# MXR_Microamp.net
KiCad netlist of a schematic drawn in EAGLE
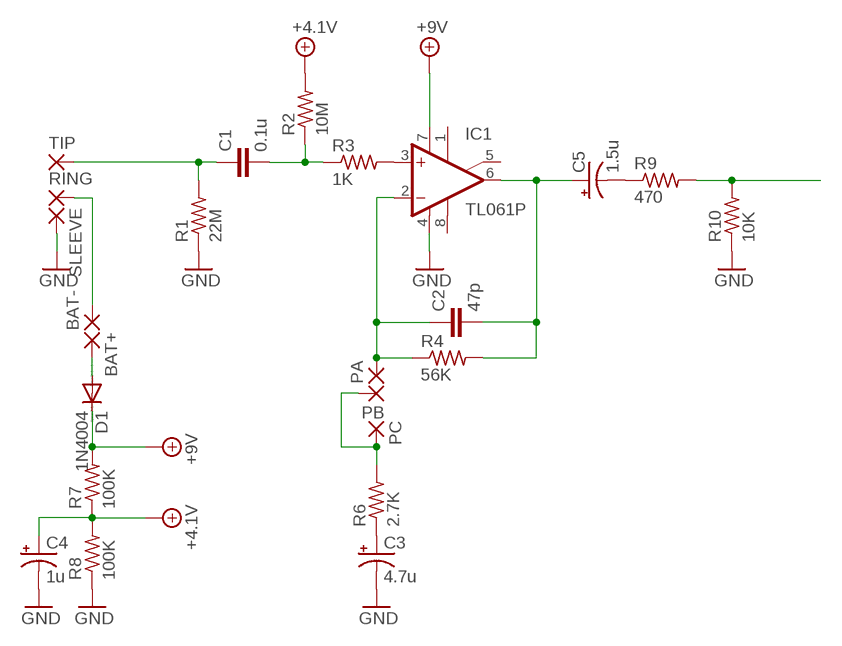
[diagram p0: schematic, sheet 1]

(export (version "E")
  (design (tool "Eeschema 10.0.6"))
  (components
    (comp (ref "BAT+")
      (value "1,6/0,8")
      (footprint "eagle-import:1,6_0,8")
      (libsource (lib "eagle-import") (part "1,6/0,8"))
    )
    (comp (ref "BAT-")
      (value "1,6/0,8")
      (footprint "eagle-import:1,6_0,8")
      (libsource (lib "eagle-import") (part "1,6/0,8"))
    )
    (comp (ref "C1")
      (value "0.1u")
      (footprint "eagle-import:C2.5-3")
      (libsource (lib "eagle-import") (part "C2,5-3"))
    )
    (comp (ref "C2")
      (value "47p")
      (footprint "eagle-import:C2.5-3")
      (libsource (lib "eagle-import") (part "C2,5-3"))
    )
    (comp (ref "C3")
      (value "4.7u")
      (footprint "eagle-import:E2,5-5")
      (libsource (lib "eagle-import") (part "CPOL-USE2.5-5"))
    )
    (comp (ref "C4")
      (value "1u")
      (footprint "eagle-import:E2,5-5")
      (libsource (lib "eagle-import") (part "CPOL-USE2.5-5"))
    )
    (comp (ref "C5")
      (value "1.5u")
      (footprint "eagle-import:E2,5-5")
      (libsource (lib "eagle-import") (part "CPOL-USE2.5-5"))
    )
    (comp (ref "D1")
      (value "1N4004")
      (footprint "eagle-import:DO41-10")
      (libsource (lib "eagle-import") (part "1N4004"))
    )
    (comp (ref "IC1")
      (value "TL061P")
      (footprint "eagle-import:DIL08")
      (libsource (lib "eagle-import") (part "TL061P"))
    )
    (comp (ref "PA")
      (value "1,6/0,8")
      (footprint "eagle-import:1,6_0,8")
      (libsource (lib "eagle-import") (part "1,6/0,8"))
    )
    (comp (ref "PB")
      (value "1,6/0,8")
      (footprint "eagle-import:1,6_0,8")
      (libsource (lib "eagle-import") (part "1,6/0,8"))
    )
    (comp (ref "PC")
      (value "1,6/0,8")
      (footprint "eagle-import:1,6_0,8")
      (libsource (lib "eagle-import") (part "1,6/0,8"))
    )
    (comp (ref "R1")
      (value "22M")
      (footprint "eagle-import:0207_7")
      (libsource (lib "eagle-import") (part "R-US_0207/7"))
    )
    (comp (ref "R2")
      (value "10M")
      (footprint "eagle-import:0207_7")
      (libsource (lib "eagle-import") (part "R-US_0207/7"))
    )
    (comp (ref "R3")
      (value "1K")
      (footprint "eagle-import:0207_7")
      (libsource (lib "eagle-import") (part "R-US_0207/7"))
    )
    (comp (ref "R4")
      (value "56K")
      (footprint "eagle-import:0207_7")
      (libsource (lib "eagle-import") (part "R-US_0207/7"))
    )
    (comp (ref "R6")
      (value "2.7K")
      (footprint "eagle-import:0207_7")
      (libsource (lib "eagle-import") (part "R-US_0207/7"))
    )
    (comp (ref "R7")
      (value "100K")
      (footprint "eagle-import:0207_7")
      (libsource (lib "eagle-import") (part "R-US_0207/7"))
    )
    (comp (ref "R8")
      (value "100K")
      (footprint "eagle-import:0207_7")
      (libsource (lib "eagle-import") (part "R-US_0207/7"))
    )
    (comp (ref "R9")
      (value "470")
      (footprint "eagle-import:0207_7")
      (libsource (lib "eagle-import") (part "R-US_0207/7"))
    )
    (comp (ref "R10")
      (value "10K")
      (footprint "eagle-import:0207_7")
      (libsource (lib "eagle-import") (part "R-US_0207/7"))
    )
    (comp (ref "RING")
      (value "1,6/0,8")
      (footprint "eagle-import:1,6_0,8")
      (libsource (lib "eagle-import") (part "1,6/0,8"))
    )
    (comp (ref "SLEEVE")
      (value "1,6/0,8")
      (footprint "eagle-import:1,6_0,8")
      (libsource (lib "eagle-import") (part "1,6/0,8"))
    )
    (comp (ref "TIP")
      (value "1,6/0,8")
      (footprint "eagle-import:1,6_0,8")
      (libsource (lib "eagle-import") (part "1,6/0,8"))
    )
  )
  (nets
    (net (code "1") (name "+4.1V") (class "Default")
      (node (ref "C4") (pin "+") (pinfunction "+_+") (pintype "passive"))
      (node (ref "R2") (pin "2") (pinfunction "2_2") (pintype "passive"))
      (node (ref "R7") (pin "1") (pinfunction "1_1") (pintype "passive"))
      (node (ref "R8") (pin "2") (pinfunction "2_2") (pintype "passive"))
    )
    (net (code "2") (name "+9V") (class "Default")
      (node (ref "D1") (pin "C") (pinfunction "C_C") (pintype "passive"))
      (node (ref "IC1") (pin "7") (pinfunction "V+_7") (pintype "power_in"))
      (node (ref "R7") (pin "2") (pinfunction "2_2") (pintype "passive"))
    )
    (net (code "3") (name "GND") (class "Default")
      (node (ref "C3") (pin "-") (pinfunction "-_-") (pintype "passive"))
      (node (ref "C4") (pin "-") (pinfunction "-_-") (pintype "passive"))
      (node (ref "IC1") (pin "4") (pinfunction "V-_4") (pintype "power_in"))
      (node (ref "R1") (pin "1") (pinfunction "1_1") (pintype "passive"))
      (node (ref "R10") (pin "1") (pinfunction "1_1") (pintype "passive"))
      (node (ref "R8") (pin "1") (pinfunction "1_1") (pintype "passive"))
      (node (ref "SLEEVE") (pin "1") (pinfunction "P_1") (pintype "passive"))
    )
    (net (code "4") (name "Net-(BAT+-P)") (class "Default")
      (node (ref "BAT+") (pin "1") (pinfunction "P_1") (pintype "passive"))
      (node (ref "D1") (pin "A") (pinfunction "A_A") (pintype "passive"))
    )
    (net (code "5") (name "Net-(BAT--P)") (class "Default")
      (node (ref "BAT-") (pin "1") (pinfunction "P_1") (pintype "passive"))
      (node (ref "RING") (pin "1") (pinfunction "P_1") (pintype "passive"))
    )
    (net (code "6") (name "Net-(C1-Pad2)") (class "Default")
      (node (ref "C1") (pin "2") (pinfunction "2_2") (pintype "passive"))
      (node (ref "R2") (pin "1") (pinfunction "1_1") (pintype "passive"))
      (node (ref "R3") (pin "1") (pinfunction "1_1") (pintype "passive"))
    )
    (net (code "7") (name "Net-(C3-Pad+)") (class "Default")
      (node (ref "C3") (pin "+") (pinfunction "+_+") (pintype "passive"))
      (node (ref "R6") (pin "1") (pinfunction "1_1") (pintype "passive"))
    )
    (net (code "8") (name "Net-(C5-Pad-)") (class "Default")
      (node (ref "C5") (pin "-") (pinfunction "-_-") (pintype "passive"))
      (node (ref "R9") (pin "1") (pinfunction "1_1") (pintype "passive"))
    )
    (net (code "9") (name "Net-(IC1-+IN)") (class "Default")
      (node (ref "IC1") (pin "3") (pinfunction "+IN_3") (pintype "input"))
      (node (ref "R3") (pin "2") (pinfunction "2_2") (pintype "passive"))
    )
    (net (code "10") (name "Net-(IC1--IN)") (class "Default")
      (node (ref "C2") (pin "1") (pinfunction "1_1") (pintype "passive"))
      (node (ref "IC1") (pin "2") (pinfunction "-IN_2") (pintype "input"))
      (node (ref "PA") (pin "1") (pinfunction "P_1") (pintype "passive"))
      (node (ref "R4") (pin "1") (pinfunction "1_1") (pintype "passive"))
    )
    (net (code "11") (name "Net-(IC1-OUT)") (class "Default")
      (node (ref "C2") (pin "2") (pinfunction "2_2") (pintype "passive"))
      (node (ref "C5") (pin "+") (pinfunction "+_+") (pintype "passive"))
      (node (ref "IC1") (pin "6") (pinfunction "OUT_6") (pintype "output"))
      (node (ref "R4") (pin "2") (pinfunction "2_2") (pintype "passive"))
    )
    (net (code "12") (name "Net-(PB-P)") (class "Default")
      (node (ref "PB") (pin "1") (pinfunction "P_1") (pintype "passive"))
      (node (ref "PC") (pin "1") (pinfunction "P_1") (pintype "passive"))
      (node (ref "R6") (pin "2") (pinfunction "2_2") (pintype "passive"))
    )
    (net (code "13") (name "Net-(R10-Pad2)") (class "Default")
      (node (ref "R10") (pin "2") (pinfunction "2_2") (pintype "passive"))
      (node (ref "R9") (pin "2") (pinfunction "2_2") (pintype "passive"))
    )
    (net (code "14") (name "Net-(TIP-P)") (class "Default")
      (node (ref "C1") (pin "1") (pinfunction "1_1") (pintype "passive"))
      (node (ref "R1") (pin "2") (pinfunction "2_2") (pintype "passive"))
      (node (ref "TIP") (pin "1") (pinfunction "P_1") (pintype "passive"))
    )
    (net (code "15") (name "unconnected-(IC1-ON1-Pad1)") (class "Default")
      (node (ref "IC1") (pin "1") (pinfunction "ON1_1") (pintype "passive"))
    )
    (net (code "16") (name "unconnected-(IC1-ON2-Pad5)") (class "Default")
      (node (ref "IC1") (pin "5") (pinfunction "ON2_5") (pintype "passive"))
    )
    (net (code "17") (name "unconnected-(IC1-OPT-Pad8)") (class "Default")
      (node (ref "IC1") (pin "8") (pinfunction "OPT_8") (pintype "passive"))
    )
  )
)
